# led.net
KiCad netlist of a schematic drawn in Altium Designer
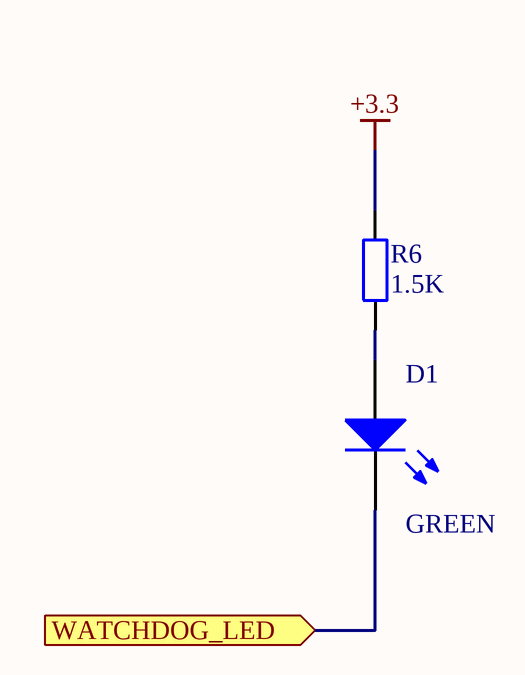
[diagram p0: led.SchDoc]

(export (version "E")
  (design (tool "Eeschema 10.0.6"))
  (components
    (comp (ref "D1")
      (value "GREEN")
      (footprint "LGQ971")
      (description "Typical RED, GREEN, YELLOW, AMBER GaAs LED")
      (libsource (lib "Miscellaneous Devices") (part "LED2"))
    )
    (comp (ref "R6")
      (value "1.5K")
      (footprint "R0603")
      (description "Resistor")
      (fields (field (name "Comment") "Res"))
      (libsource (lib "Miscellaneous Devices") (part "Res2"))
    )
  )
  (nets
    (net (code "1") (name "+3.3") (class "Default")
      (node (ref "R6") (pin "2") (pinfunction "2_2") (pintype "passive"))
    )
    (net (code "2") (name "/WATCHDOG_LED") (class "Default")
      (node (ref "D1") (pin "2") (pinfunction "K_2") (pintype "passive"))
    )
    (net (code "3") (name "Net-(D1-A)") (class "Default")
      (node (ref "D1") (pin "1") (pinfunction "A_1") (pintype "passive"))
      (node (ref "R6") (pin "1") (pinfunction "1_1") (pintype "passive"))
    )
  )
)
